# top.net
KiCad netlist of a schematic drawn in EAGLE
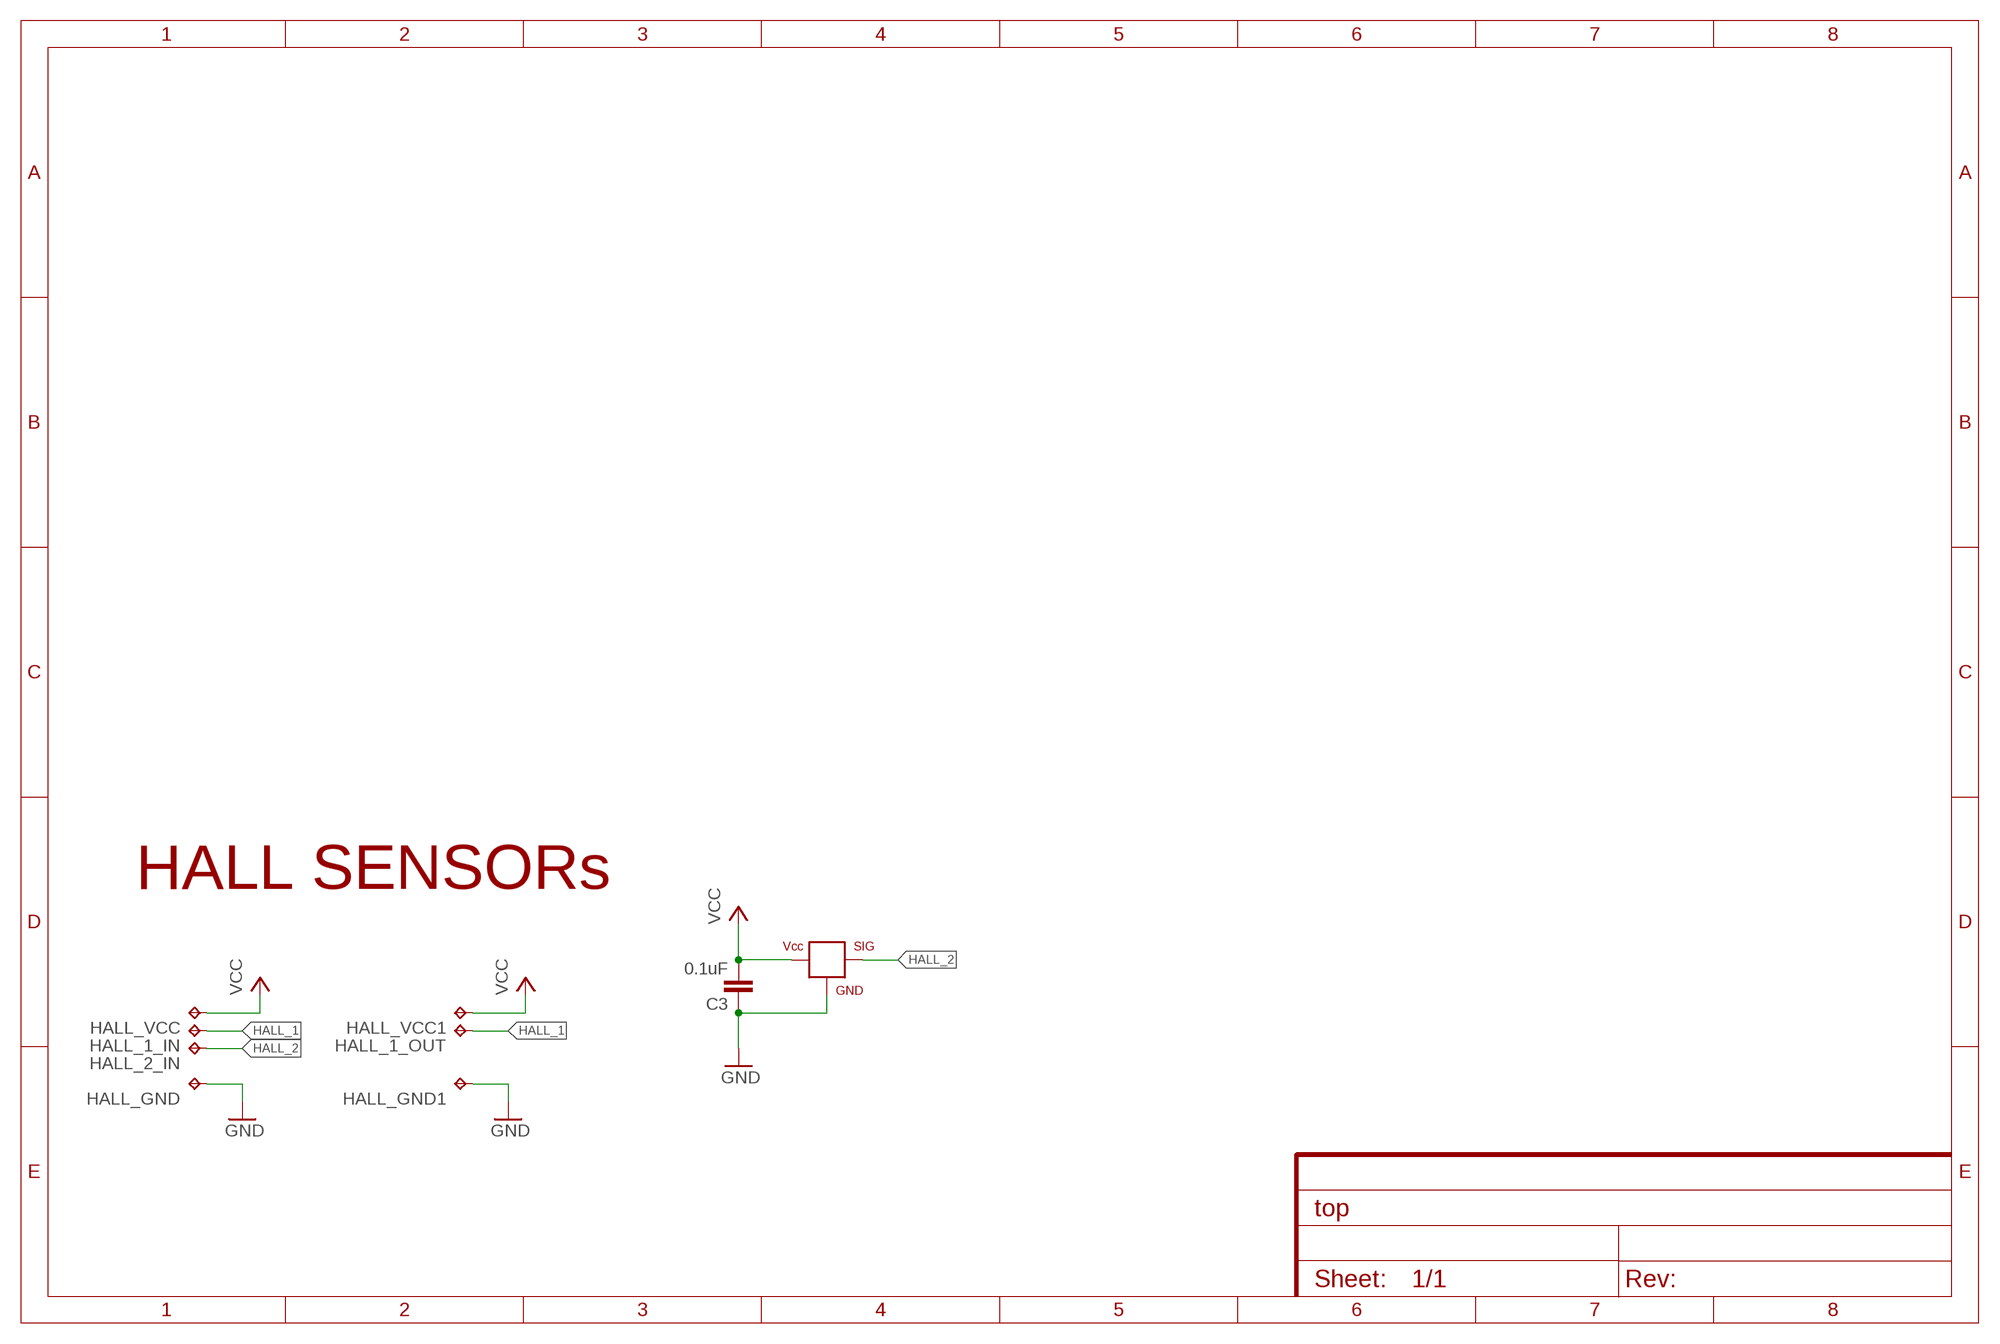
[diagram p0: schematic, sheet 1]

(export (version "E")
  (design (tool "Eeschema 10.0.6"))
  (components
    (comp (ref "C3")
      (value "0.1uF")
      (footprint "eagle-import:0603-CAP")
      (libsource (lib "eagle-import") (part "CAP0603-CAP"))
    )
    (comp (ref "HALL")
      (value "HALLEFFECT-A1326")
      (footprint "eagle-import:SOT23-3")
      (libsource (lib "eagle-import") (part "HALLEFFECT-A1326"))
    )
    (comp (ref "HALL_1_IN")
      (value "TPTP20SQ")
      (footprint "eagle-import:TP20SQ")
      (libsource (lib "eagle-import") (part "TPTP20SQ"))
    )
    (comp (ref "HALL_1_OUT")
      (value "TPTP20SQ")
      (footprint "eagle-import:TP20SQ")
      (libsource (lib "eagle-import") (part "TPTP20SQ"))
    )
    (comp (ref "HALL_2_IN")
      (value "TPTP20SQ")
      (footprint "eagle-import:TP20SQ")
      (libsource (lib "eagle-import") (part "TPTP20SQ"))
    )
    (comp (ref "HALL_GND")
      (value "TPTP20SQ")
      (footprint "eagle-import:TP20SQ")
      (libsource (lib "eagle-import") (part "TPTP20SQ"))
    )
    (comp (ref "HALL_GND1")
      (value "TPTP20SQ")
      (footprint "eagle-import:TP20SQ")
      (libsource (lib "eagle-import") (part "TPTP20SQ"))
    )
    (comp (ref "HALL_VCC")
      (value "TPTP20SQ")
      (footprint "eagle-import:TP20SQ")
      (libsource (lib "eagle-import") (part "TPTP20SQ"))
    )
    (comp (ref "HALL_VCC1")
      (value "TPTP20SQ")
      (footprint "eagle-import:TP20SQ")
      (libsource (lib "eagle-import") (part "TPTP20SQ"))
    )
  )
  (nets
    (net (code "1") (name "GND") (class "Default")
      (node (ref "C3") (pin "1") (pinfunction "1_1") (pintype "passive"))
      (node (ref "HALL") (pin "3") (pinfunction "GND_3") (pintype "bidirectional"))
      (node (ref "HALL_GND") (pin "TP") (pinfunction "TP_TP") (pintype "input"))
      (node (ref "HALL_GND1") (pin "TP") (pinfunction "TP_TP") (pintype "input"))
    )
    (net (code "2") (name "HALL_1") (class "Default")
      (node (ref "HALL_1_IN") (pin "TP") (pinfunction "TP_TP") (pintype "input"))
      (node (ref "HALL_1_OUT") (pin "TP") (pinfunction "TP_TP") (pintype "input"))
    )
    (net (code "3") (name "HALL_2") (class "Default")
      (node (ref "HALL") (pin "2") (pinfunction "SIG_2") (pintype "bidirectional"))
      (node (ref "HALL_2_IN") (pin "TP") (pinfunction "TP_TP") (pintype "input"))
    )
    (net (code "4") (name "VCC") (class "Default")
      (node (ref "C3") (pin "2") (pinfunction "2_2") (pintype "passive"))
      (node (ref "HALL") (pin "1") (pinfunction "VCC_1") (pintype "bidirectional"))
      (node (ref "HALL_VCC") (pin "TP") (pinfunction "TP_TP") (pintype "input"))
      (node (ref "HALL_VCC1") (pin "TP") (pinfunction "TP_TP") (pintype "input"))
    )
  )
)
